# USBHeaders.net
KiCad netlist of a schematic drawn in Altium Designer
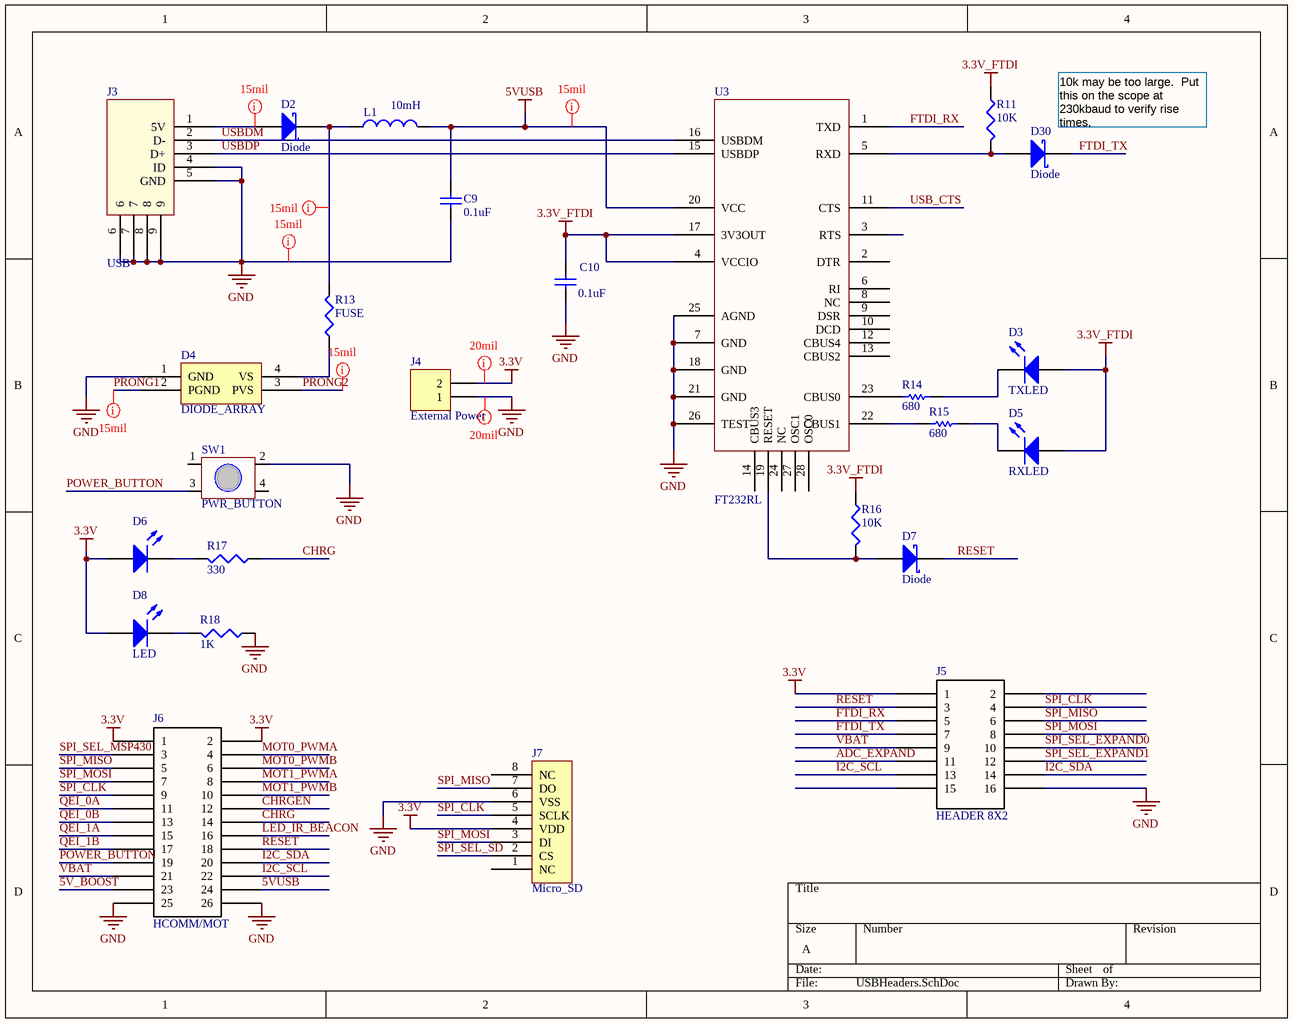
[diagram p0: USBHeaders.SchDoc]

(export (version "E")
  (design (tool "Eeschema 10.0.6"))
  (components
    (comp (ref "C9")
      (value "0.1uF")
      (footprint "CAPC1005L")
      (description "Capacitor")
      (fields (field (name "PUBLISHER") "Altium Limited"))
      (libsource (lib "Miscellaneous Devices") (part "Cap"))
    )
    (comp (ref "C10")
      (value "0.1uF")
      (footprint "CAPC1005L")
      (description "Capacitor")
      (fields (field (name "PUBLISHER") "Altium Limited"))
      (libsource (lib "Miscellaneous Devices") (part "Cap"))
    )
    (comp (ref "D2")
      (value "Diode")
      (footprint "SurfaceMount(603)")
      (libsource (lib "mrone") (part "SchottkeyDiode"))
    )
    (comp (ref "D3")
      (value "TXLED")
      (footprint "INDC2012L")
      (description "Typical RED, GREEN, YELLOW, AMBER GaAs LED")
      (fields (field (name "PUBLISHER") "Altium Limited"))
      (libsource (lib "Miscellaneous Devices") (part "LED2"))
    )
    (comp (ref "D4")
      (value "DIODE_ARRAY")
      (footprint "SOT143")
      (libsource (lib "mrone") (part "SCHOTTKEY_DIODE_ARRAY"))
    )
    (comp (ref "D5")
      (value "RXLED")
      (footprint "INDC2012L")
      (description "Typical RED, GREEN, YELLOW, AMBER GaAs LED")
      (fields (field (name "PUBLISHER") "Altium Limited"))
      (libsource (lib "Miscellaneous Devices") (part "LED2"))
    )
    (comp (ref "D6")
      (value "Charge")
      (footprint "INDC2012L")
      (description "Typical RED, GREEN, YELLOW, AMBER GaAs LED")
      (fields (field (name "PUBLISHER") "Altium Limited"))
      (libsource (lib "") (part "LED2_1"))
    )
    (comp (ref "D7")
      (value "Diode")
      (footprint "SurfaceMount(603)")
      (libsource (lib "mrone") (part "SchottkeyDiode"))
    )
    (comp (ref "D8") (value "LED") (footprint "SurfaceMount(603)") (libsource (lib "mrone") (part "LED")))
    (comp (ref "D30")
      (value "Diode")
      (footprint "SurfaceMount(603)")
      (libsource (lib "mrone") (part "SchottkeyDiode"))
    )
    (comp (ref "J3")
      (value "USB")
      (footprint "USB Minib (thru-hole)")
      (libsource (lib "mrone") (part "USB-ConnTH"))
    )
    (comp (ref "J4")
      (value "External Power")
      (footprint "HDR1X2")
      (description "Header, 2-Pin")
      (fields (field (name "PUBLISHER") "Altium Limited"))
      (libsource (lib "Miscellaneous Connectors") (part "Header 2"))
    )
    (comp (ref "J5")
      (value "HEADER 8X2")
      (footprint "HEADERSM 8X2")
      (libsource (lib "mrone") (part "HEADERS 8X2"))
    )
    (comp (ref "J6")
      (value "HCOMM/MOT")
      (footprint "HeaderSM 13x2")
      (description "Header, 2X20, 50mil, IDC")
      (libsource (lib "mrone") (part "HCOMM/HMOT"))
    )
    (comp (ref "J7") (value "Micro_SD") (footprint "MICRO_SD") (libsource (lib "mrone") (part "MICRO_SD")))
    (comp (ref "L1")
      (value "10mH")
      (footprint "INDC2012L")
      (description "Inductor")
      (fields (field (name "PUBLISHER") "Altium Limited"))
      (libsource (lib "Miscellaneous Devices") (part "Inductor"))
    )
    (comp (ref "R11")
      (value "10K")
      (footprint "RESC1608L")
      (description "Resistor")
      (fields (field (name "Comment") "Res3") (field (name "PUBLISHER") "Altium Limited"))
      (libsource (lib "Miscellaneous Devices") (part "Res3"))
    )
    (comp (ref "R13")
      (value "FUSE")
      (footprint "RESC3225L")
      (description "Resistor")
      (fields (field (name "Comment") "Res3") (field (name "PUBLISHER") "Altium Limited"))
      (libsource (lib "Miscellaneous Devices") (part "Res3"))
    )
    (comp (ref "R14")
      (value "680")
      (footprint "RESC1608L")
      (description "Resistor")
      (fields (field (name "PUBLISHER") "Altium Limited"))
      (libsource (lib "Miscellaneous Devices") (part "Res1"))
    )
    (comp (ref "R15")
      (value "680")
      (footprint "RESC1608L")
      (description "Resistor")
      (fields (field (name "PUBLISHER") "Altium Limited"))
      (libsource (lib "Miscellaneous Devices") (part "Res1"))
    )
    (comp (ref "R16")
      (value "10K")
      (footprint "RESC1608L")
      (description "Resistor")
      (fields (field (name "Comment") "Res3") (field (name "PUBLISHER") "Altium Limited"))
      (libsource (lib "Miscellaneous Devices") (part "Res3"))
    )
    (comp (ref "R17")
      (value "330")
      (footprint "RESC1608L")
      (description "Resistor")
      (fields (field (name "Comment") "Res3") (field (name "PUBLISHER") "Altium Limited"))
      (libsource (lib "Miscellaneous Devices") (part "Res3"))
    )
    (comp (ref "R18")
      (value "1K")
      (footprint "RESC1608L")
      (description "Resistor")
      (fields (field (name "Comment") "Res3") (field (name "PUBLISHER") "Altium Limited"))
      (libsource (lib "Miscellaneous Devices") (part "Res3"))
    )
    (comp (ref "SW1")
      (value "PWR_BUTTON")
      (footprint "SwitchTall-TL330")
      (libsource (lib "mrone") (part "Switch-TL330"))
    )
    (comp (ref "U3") (value "FT232RL") (footprint "SSOP-28") (libsource (lib "mrone") (part "FT232RL")))
  )
  (nets
    (net (code "1") (name "/5V_BOOST") (class "Default")
      (node (ref "J6") (pin "23") (pinfunction "23_23") (pintype "passive"))
    )
    (net (code "3") (name "/ADC_EXPAND") (class "Default")
      (node (ref "J5") (pin "11") (pinfunction "11_11") (pintype "passive"))
    )
    (net (code "4") (name "/CHRG") (class "Default")
      (node (ref "J6") (pin "14") (pinfunction "14_14") (pintype "passive"))
      (node (ref "R17") (pin "1") (pinfunction "1_1") (pintype "passive"))
    )
    (net (code "5") (name "/CHRGEN") (class "Default")
      (node (ref "J6") (pin "12") (pinfunction "12_12") (pintype "passive"))
    )
    (net (code "6") (name "/FTDI_RX") (class "Default")
      (node (ref "J5") (pin "5") (pinfunction "5_5") (pintype "passive"))
      (node (ref "U3") (pin "1") (pinfunction "TXD_1") (pintype "passive"))
    )
    (net (code "7") (name "/FTDI_TX") (class "Default")
      (node (ref "D30") (pin "1") (pinfunction "K_1") (pintype "passive"))
      (node (ref "J5") (pin "7") (pinfunction "7_7") (pintype "passive"))
    )
    (net (code "8") (name "/I2C_SCL") (class "Default")
      (node (ref "J5") (pin "13") (pinfunction "13_13") (pintype "passive"))
      (node (ref "J6") (pin "22") (pinfunction "22_22") (pintype "passive"))
    )
    (net (code "9") (name "/I2C_SDA") (class "Default")
      (node (ref "J5") (pin "14") (pinfunction "14_14") (pintype "passive"))
      (node (ref "J6") (pin "20") (pinfunction "20_20") (pintype "passive"))
    )
    (net (code "10") (name "/LED_IR_BEACON") (class "Default")
      (node (ref "J6") (pin "16") (pinfunction "16_16") (pintype "passive"))
    )
    (net (code "11") (name "/MOT0_PWMA") (class "Default")
      (node (ref "J6") (pin "4") (pinfunction "4_4") (pintype "passive"))
    )
    (net (code "12") (name "/MOT0_PWMB") (class "Default")
      (node (ref "J6") (pin "6") (pinfunction "6_6") (pintype "passive"))
    )
    (net (code "13") (name "/MOT1_PWMA") (class "Default")
      (node (ref "J6") (pin "8") (pinfunction "8_8") (pintype "passive"))
    )
    (net (code "14") (name "/MOT1_PWMB") (class "Default")
      (node (ref "J6") (pin "10") (pinfunction "10_10") (pintype "passive"))
    )
    (net (code "15") (name "/POWER_BUTTON") (class "Default")
      (node (ref "J6") (pin "19") (pinfunction "19_19") (pintype "passive"))
      (node (ref "SW1") (pin "3") (pinfunction "3_3") (pintype "passive"))
    )
    (net (code "16") (name "/PRONG1") (class "Default")
      (node (ref "D4") (pin "2") (pinfunction "PGND_2") (pintype "passive"))
    )
    (net (code "17") (name "/PRONG2") (class "Default")
      (node (ref "D4") (pin "3") (pinfunction "PVS_3") (pintype "passive"))
    )
    (net (code "18") (name "/QEI_0A") (class "Default")
      (node (ref "J6") (pin "11") (pinfunction "11_11") (pintype "passive"))
    )
    (net (code "19") (name "/QEI_0B") (class "Default")
      (node (ref "J6") (pin "13") (pinfunction "13_13") (pintype "passive"))
    )
    (net (code "20") (name "/QEI_1A") (class "Default")
      (node (ref "J6") (pin "15") (pinfunction "15_15") (pintype "passive"))
    )
    (net (code "21") (name "/QEI_1B") (class "Default")
      (node (ref "J6") (pin "17") (pinfunction "17_17") (pintype "passive"))
    )
    (net (code "22") (name "/RESET") (class "Default")
      (node (ref "D7") (pin "1") (pinfunction "K_1") (pintype "passive"))
      (node (ref "J5") (pin "3") (pinfunction "3_3") (pintype "passive"))
      (node (ref "J6") (pin "18") (pinfunction "18_18") (pintype "passive"))
    )
    (net (code "23") (name "/SPI_CLK") (class "Default")
      (node (ref "J5") (pin "4") (pinfunction "4_4") (pintype "passive"))
      (node (ref "J6") (pin "9") (pinfunction "9_9") (pintype "passive"))
      (node (ref "J7") (pin "5") (pinfunction "SCLK_5") (pintype "passive"))
    )
    (net (code "24") (name "/SPI_MISO") (class "Default")
      (node (ref "J5") (pin "6") (pinfunction "6_6") (pintype "passive"))
      (node (ref "J6") (pin "5") (pinfunction "5_5") (pintype "passive"))
      (node (ref "J7") (pin "7") (pinfunction "DO_7") (pintype "passive"))
    )
    (net (code "25") (name "/SPI_MOSI") (class "Default")
      (node (ref "J5") (pin "8") (pinfunction "8_8") (pintype "passive"))
      (node (ref "J6") (pin "7") (pinfunction "7_7") (pintype "passive"))
      (node (ref "J7") (pin "3") (pinfunction "DI_3") (pintype "passive"))
    )
    (net (code "26") (name "/SPI_SEL_EXPAND0") (class "Default")
      (node (ref "J5") (pin "10") (pinfunction "10_10") (pintype "passive"))
    )
    (net (code "27") (name "/SPI_SEL_EXPAND1") (class "Default")
      (node (ref "J5") (pin "12") (pinfunction "12_12") (pintype "passive"))
    )
    (net (code "28") (name "/SPI_SEL_MSP430") (class "Default")
      (node (ref "J6") (pin "3") (pinfunction "3_3") (pintype "passive"))
    )
    (net (code "29") (name "/SPI_SEL_SD") (class "Default")
      (node (ref "J7") (pin "2") (pinfunction "CS_2") (pintype "passive"))
    )
    (net (code "30") (name "/USBDM") (class "Default")
      (node (ref "J3") (pin "2") (pinfunction "D-_2") (pintype "passive"))
      (node (ref "U3") (pin "16") (pinfunction "USBDM_16") (pintype "passive"))
    )
    (net (code "31") (name "/USBDP") (class "Default")
      (node (ref "J3") (pin "3") (pinfunction "D+_3") (pintype "passive"))
      (node (ref "U3") (pin "15") (pinfunction "USBDP_15") (pintype "passive"))
    )
    (net (code "32") (name "/USB_CTS") (class "Default")
      (node (ref "U3") (pin "11") (pinfunction "CTS_11") (pintype "passive"))
    )
    (net (code "33") (name "/VBAT") (class "Default")
      (node (ref "J5") (pin "9") (pinfunction "9_9") (pintype "passive"))
      (node (ref "J6") (pin "21") (pinfunction "21_21") (pintype "passive"))
    )
    (net (code "34") (name "3.3V") (class "Default")
      (node (ref "D6") (pin "1") (pinfunction "A_1") (pintype "passive"))
      (node (ref "D8") (pin "1") (pinfunction "A_1") (pintype "passive"))
      (node (ref "J4") (pin "2") (pinfunction "2_2") (pintype "passive"))
      (node (ref "J5") (pin "1") (pinfunction "1_1") (pintype "passive"))
      (node (ref "J6") (pin "1") (pinfunction "1_1") (pintype "passive"))
      (node (ref "J6") (pin "2") (pinfunction "2_2") (pintype "passive"))
      (node (ref "J7") (pin "4") (pinfunction "VDD_4") (pintype "passive"))
    )
    (net (code "35") (name "3.3V_FTDI") (class "Default")
      (node (ref "C10") (pin "2") (pinfunction "2_2") (pintype "passive"))
      (node (ref "D3") (pin "1") (pinfunction "A_1") (pintype "passive"))
      (node (ref "D5") (pin "1") (pinfunction "A_1") (pintype "passive"))
      (node (ref "R11") (pin "1") (pinfunction "1_1") (pintype "passive"))
      (node (ref "R16") (pin "1") (pinfunction "1_1") (pintype "passive"))
      (node (ref "U3") (pin "17") (pinfunction "3V3OUT_17") (pintype "passive"))
      (node (ref "U3") (pin "4") (pinfunction "VCCIO_4") (pintype "passive"))
    )
    (net (code "36") (name "5VUSB") (class "Default")
      (node (ref "C9") (pin "2") (pinfunction "2_2") (pintype "passive"))
      (node (ref "J6") (pin "24") (pinfunction "24_24") (pintype "passive"))
      (node (ref "L1") (pin "2") (pinfunction "2_2") (pintype "passive"))
      (node (ref "U3") (pin "20") (pinfunction "VCC_20") (pintype "passive"))
    )
    (net (code "37") (name "GND") (class "Default")
      (node (ref "C10") (pin "1") (pinfunction "1_1") (pintype "passive"))
      (node (ref "C9") (pin "1") (pinfunction "1_1") (pintype "passive"))
      (node (ref "D4") (pin "1") (pinfunction "GND_1") (pintype "passive"))
      (node (ref "J3") (pin "4") (pinfunction "ID_4") (pintype "passive"))
      (node (ref "J3") (pin "5") (pinfunction "GND_5") (pintype "passive"))
      (node (ref "J3") (pin "6") (pinfunction "6_6") (pintype "passive"))
      (node (ref "J3") (pin "7") (pinfunction "7_7") (pintype "passive"))
      (node (ref "J3") (pin "8") (pinfunction "8_8") (pintype "passive"))
      (node (ref "J3") (pin "9") (pinfunction "9_9") (pintype "passive"))
      (node (ref "J4") (pin "1") (pinfunction "1_1") (pintype "passive"))
      (node (ref "J5") (pin "16") (pinfunction "16_16") (pintype "passive"))
      (node (ref "J6") (pin "25") (pinfunction "25_25") (pintype "passive"))
      (node (ref "J6") (pin "26") (pinfunction "26_26") (pintype "passive"))
      (node (ref "J7") (pin "6") (pinfunction "VSS_6") (pintype "passive"))
      (node (ref "R18") (pin "1") (pinfunction "1_1") (pintype "passive"))
      (node (ref "SW1") (pin "2") (pinfunction "2_2") (pintype "passive"))
      (node (ref "U3") (pin "18") (pinfunction "GND_18") (pintype "passive"))
      (node (ref "U3") (pin "21") (pinfunction "GND_21") (pintype "passive"))
      (node (ref "U3") (pin "25") (pinfunction "AGND_25") (pintype "passive"))
      (node (ref "U3") (pin "26") (pinfunction "TEST_26") (pintype "passive"))
      (node (ref "U3") (pin "7") (pinfunction "GND_7") (pintype "passive"))
    )
    (net (code "38") (name "Net-(D2-A)") (class "Default")
      (node (ref "D2") (pin "2") (pinfunction "A_2") (pintype "passive"))
      (node (ref "J3") (pin "1") (pinfunction "5V_1") (pintype "passive"))
    )
    (net (code "39") (name "Net-(D2-K)") (class "Default")
      (node (ref "D2") (pin "1") (pinfunction "K_1") (pintype "passive"))
      (node (ref "L1") (pin "1") (pinfunction "1_1") (pintype "passive"))
      (node (ref "R13") (pin "2") (pinfunction "2_2") (pintype "passive"))
    )
    (net (code "40") (name "Net-(D3-K)") (class "Default")
      (node (ref "D3") (pin "2") (pinfunction "K_2") (pintype "passive"))
      (node (ref "R14") (pin "2") (pinfunction "2_2") (pintype "passive"))
    )
    (net (code "41") (name "Net-(D4-VS)") (class "Default")
      (node (ref "D4") (pin "4") (pinfunction "VS_4") (pintype "passive"))
      (node (ref "R13") (pin "1") (pinfunction "1_1") (pintype "passive"))
    )
    (net (code "42") (name "Net-(D5-K)") (class "Default")
      (node (ref "D5") (pin "2") (pinfunction "K_2") (pintype "passive"))
      (node (ref "R15") (pin "2") (pinfunction "2_2") (pintype "passive"))
    )
    (net (code "43") (name "Net-(D6-K)") (class "Default")
      (node (ref "D6") (pin "2") (pinfunction "K_2") (pintype "passive"))
      (node (ref "R17") (pin "2") (pinfunction "2_2") (pintype "passive"))
    )
    (net (code "44") (name "Net-(D7-A)") (class "Default")
      (node (ref "D7") (pin "2") (pinfunction "A_2") (pintype "passive"))
      (node (ref "R16") (pin "2") (pinfunction "2_2") (pintype "passive"))
      (node (ref "U3") (pin "19") (pinfunction "RESET_19") (pintype "passive"))
    )
    (net (code "45") (name "Net-(D8-K)") (class "Default")
      (node (ref "D8") (pin "2") (pinfunction "K_2") (pintype "passive"))
      (node (ref "R18") (pin "2") (pinfunction "2_2") (pintype "passive"))
    )
    (net (code "46") (name "Net-(D30-A)") (class "Default")
      (node (ref "D30") (pin "2") (pinfunction "A_2") (pintype "passive"))
      (node (ref "R11") (pin "2") (pinfunction "2_2") (pintype "passive"))
      (node (ref "U3") (pin "5") (pinfunction "RXD_5") (pintype "passive"))
    )
    (net (code "47") (name "Net-(U3-CBUS0)") (class "Default")
      (node (ref "R14") (pin "1") (pinfunction "1_1") (pintype "passive"))
      (node (ref "U3") (pin "23") (pinfunction "CBUS0_23") (pintype "passive"))
    )
    (net (code "48") (name "Net-(U3-CBUS1)") (class "Default")
      (node (ref "R15") (pin "1") (pinfunction "1_1") (pintype "passive"))
      (node (ref "U3") (pin "22") (pinfunction "CBUS1_22") (pintype "passive"))
    )
    (net (code "49") (name "unconnected-(J5-Pad2)") (class "Default")
      (node (ref "J5") (pin "2") (pinfunction "2_2") (pintype "passive"))
    )
    (net (code "50") (name "unconnected-(J5-Pad15)") (class "Default")
      (node (ref "J5") (pin "15") (pinfunction "15_15") (pintype "passive"))
    )
    (net (code "51") (name "unconnected-(J7-NC-Pad1)") (class "Default")
      (node (ref "J7") (pin "1") (pinfunction "NC_1") (pintype "passive"))
    )
    (net (code "52") (name "unconnected-(J7-NC-Pad8)") (class "Default")
      (node (ref "J7") (pin "8") (pinfunction "NC_8") (pintype "passive"))
    )
    (net (code "53") (name "unconnected-(SW1-Pad1)") (class "Default")
      (node (ref "SW1") (pin "1") (pinfunction "1_1") (pintype "passive"))
    )
    (net (code "54") (name "unconnected-(SW1-Pad4)") (class "Default")
      (node (ref "SW1") (pin "4") (pinfunction "4_4") (pintype "passive"))
    )
    (net (code "55") (name "unconnected-(U3-CBUS2-Pad13)") (class "Default")
      (node (ref "U3") (pin "13") (pinfunction "CBUS2_13") (pintype "passive"))
    )
    (net (code "56") (name "unconnected-(U3-CBUS3-Pad14)") (class "Default")
      (node (ref "U3") (pin "14") (pinfunction "CBUS3_14") (pintype "passive"))
    )
    (net (code "57") (name "unconnected-(U3-CBUS4-Pad12)") (class "Default")
      (node (ref "U3") (pin "12") (pinfunction "CBUS4_12") (pintype "passive"))
    )
    (net (code "58") (name "unconnected-(U3-DCD-Pad10)") (class "Default")
      (node (ref "U3") (pin "10") (pinfunction "DCD_10") (pintype "passive"))
    )
    (net (code "59") (name "unconnected-(U3-DSR-Pad9)") (class "Default")
      (node (ref "U3") (pin "9") (pinfunction "DSR_9") (pintype "passive"))
    )
    (net (code "60") (name "unconnected-(U3-DTR-Pad2)") (class "Default")
      (node (ref "U3") (pin "2") (pinfunction "DTR_2") (pintype "passive"))
    )
    (net (code "61") (name "unconnected-(U3-NC-Pad8)") (class "Default")
      (node (ref "U3") (pin "8") (pinfunction "NC_8") (pintype "passive"))
    )
    (net (code "62") (name "unconnected-(U3-NC-Pad24)") (class "Default")
      (node (ref "U3") (pin "24") (pinfunction "NC_24") (pintype "passive"))
    )
    (net (code "63") (name "unconnected-(U3-OSC0-Pad28)") (class "Default")
      (node (ref "U3") (pin "28") (pinfunction "OSC0_28") (pintype "passive"))
    )
    (net (code "64") (name "unconnected-(U3-OSC1-Pad27)") (class "Default")
      (node (ref "U3") (pin "27") (pinfunction "OSC1_27") (pintype "passive"))
    )
    (net (code "65") (name "unconnected-(U3-RI-Pad6)") (class "Default")
      (node (ref "U3") (pin "6") (pinfunction "RI_6") (pintype "passive"))
    )
    (net (code "66") (name "unconnected-(U3-RTS-Pad3)") (class "Default")
      (node (ref "U3") (pin "3") (pinfunction "RTS_3") (pintype "passive"))
    )
  )
)
